# 130_adapt.net
KiCad netlist of a schematic drawn in EAGLE
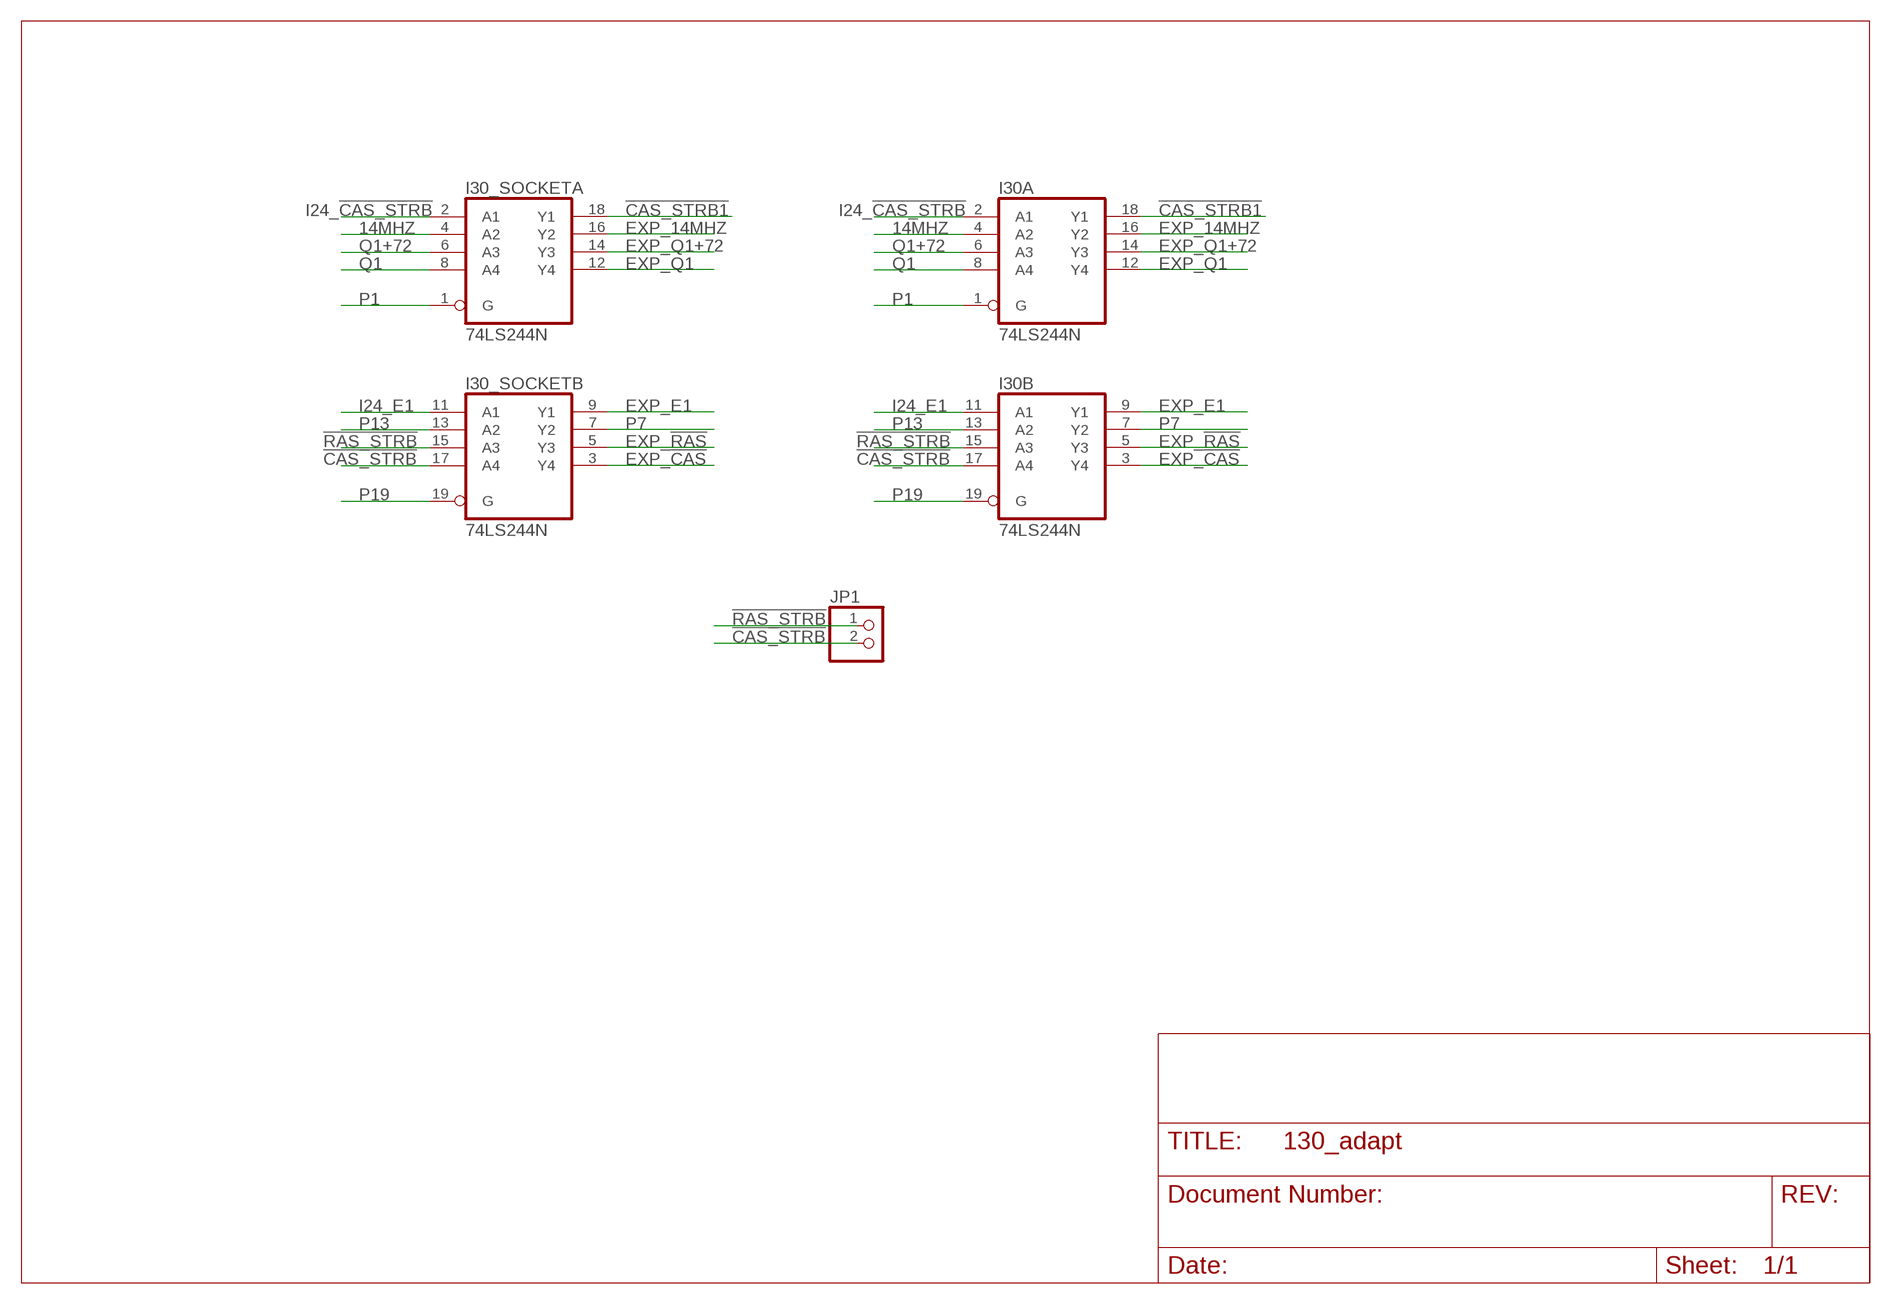
[diagram p0: schematic, sheet 1]

(export (version "E")
  (design (tool "Eeschema 10.0.6"))
  (components
    (comp (ref "I30")
      (value "74LS244N")
      (footprint "eagle-import:DIL20")
      (libsource (lib "eagle-import") (part "74244NLS"))
    )
    (comp (ref "I30_SOCKET")
      (value "74LS244N")
      (footprint "eagle-import:DIL20")
      (libsource (lib "eagle-import") (part "74244NLS"))
    )
    (comp (ref "JP1")
      (value "PINHD-1X2/90")
      (footprint "eagle-import:1X02_90")
      (libsource (lib "eagle-import") (part "PINHD-1X2/90"))
    )
  )
  (nets
    (net (code "1") (name "/14MHZ") (class "Default")
      (node (ref "I30") (pin "4") (pinfunction "A2_4") (pintype "input"))
      (node (ref "I30_SOCKET") (pin "4") (pinfunction "A2_4") (pintype "input"))
    )
    (net (code "2") (name "/EXP_14MHZ") (class "Default")
      (node (ref "I30") (pin "16") (pinfunction "Y2_16") (pintype "tri_state"))
      (node (ref "I30_SOCKET") (pin "16") (pinfunction "Y2_16") (pintype "tri_state"))
    )
    (net (code "3") (name "/EXP_E1") (class "Default")
      (node (ref "I30") (pin "9") (pinfunction "Y1_9") (pintype "tri_state"))
      (node (ref "I30_SOCKET") (pin "9") (pinfunction "Y1_9") (pintype "tri_state"))
    )
    (net (code "4") (name "/EXP_Q1") (class "Default")
      (node (ref "I30") (pin "12") (pinfunction "Y4_12") (pintype "tri_state"))
      (node (ref "I30_SOCKET") (pin "12") (pinfunction "Y4_12") (pintype "tri_state"))
    )
    (net (code "5") (name "/EXP_Q1+72") (class "Default")
      (node (ref "I30") (pin "14") (pinfunction "Y3_14") (pintype "tri_state"))
      (node (ref "I30_SOCKET") (pin "14") (pinfunction "Y3_14") (pintype "tri_state"))
    )
    (net (code "6") (name "/EXP_~{CAS}") (class "Default")
      (node (ref "I30") (pin "3") (pinfunction "Y4_3") (pintype "tri_state"))
      (node (ref "I30_SOCKET") (pin "3") (pinfunction "Y4_3") (pintype "tri_state"))
    )
    (net (code "7") (name "/EXP_~{RAS}") (class "Default")
      (node (ref "I30") (pin "5") (pinfunction "Y3_5") (pintype "tri_state"))
      (node (ref "I30_SOCKET") (pin "5") (pinfunction "Y3_5") (pintype "tri_state"))
    )
    (net (code "8") (name "/I24_E1") (class "Default")
      (node (ref "I30") (pin "11") (pinfunction "A1_11") (pintype "input"))
      (node (ref "I30_SOCKET") (pin "11") (pinfunction "A1_11") (pintype "input"))
    )
    (net (code "9") (name "/I24_~{CAS_STRB}") (class "Default")
      (node (ref "I30") (pin "2") (pinfunction "A1_2") (pintype "input"))
      (node (ref "I30_SOCKET") (pin "2") (pinfunction "A1_2") (pintype "input"))
    )
    (net (code "10") (name "/P1") (class "Default")
      (node (ref "I30") (pin "1") (pinfunction "G_1") (pintype "input"))
      (node (ref "I30_SOCKET") (pin "1") (pinfunction "G_1") (pintype "input"))
    )
    (net (code "11") (name "/P7") (class "Default")
      (node (ref "I30") (pin "7") (pinfunction "Y2_7") (pintype "tri_state"))
      (node (ref "I30_SOCKET") (pin "7") (pinfunction "Y2_7") (pintype "tri_state"))
    )
    (net (code "12") (name "/P13") (class "Default")
      (node (ref "I30") (pin "13") (pinfunction "A2_13") (pintype "input"))
      (node (ref "I30_SOCKET") (pin "13") (pinfunction "A2_13") (pintype "input"))
    )
    (net (code "13") (name "/P19") (class "Default")
      (node (ref "I30") (pin "19") (pinfunction "G_19") (pintype "input"))
      (node (ref "I30_SOCKET") (pin "19") (pinfunction "G_19") (pintype "input"))
    )
    (net (code "14") (name "/Q1") (class "Default")
      (node (ref "I30") (pin "8") (pinfunction "A4_8") (pintype "input"))
      (node (ref "I30_SOCKET") (pin "8") (pinfunction "A4_8") (pintype "input"))
    )
    (net (code "15") (name "/Q1+72") (class "Default")
      (node (ref "I30") (pin "6") (pinfunction "A3_6") (pintype "input"))
      (node (ref "I30_SOCKET") (pin "6") (pinfunction "A3_6") (pintype "input"))
    )
    (net (code "16") (name "/~{CAS_STRB1}") (class "Default")
      (node (ref "I30") (pin "18") (pinfunction "Y1_18") (pintype "tri_state"))
      (node (ref "I30_SOCKET") (pin "18") (pinfunction "Y1_18") (pintype "tri_state"))
    )
    (net (code "17") (name "/~{CAS_STRB}") (class "Default")
      (node (ref "I30") (pin "17") (pinfunction "A4_17") (pintype "input"))
      (node (ref "I30_SOCKET") (pin "17") (pinfunction "A4_17") (pintype "input"))
      (node (ref "JP1") (pin "2") (pinfunction "2_2") (pintype "passive"))
    )
    (net (code "18") (name "/~{RAS_STRB}") (class "Default")
      (node (ref "I30") (pin "15") (pinfunction "A3_15") (pintype "input"))
      (node (ref "I30_SOCKET") (pin "15") (pinfunction "A3_15") (pintype "input"))
      (node (ref "JP1") (pin "1") (pinfunction "1_1") (pintype "passive"))
    )
  )
)
